# 09_FPGA_misc.net
KiCad netlist of a schematic drawn in Altium Designer
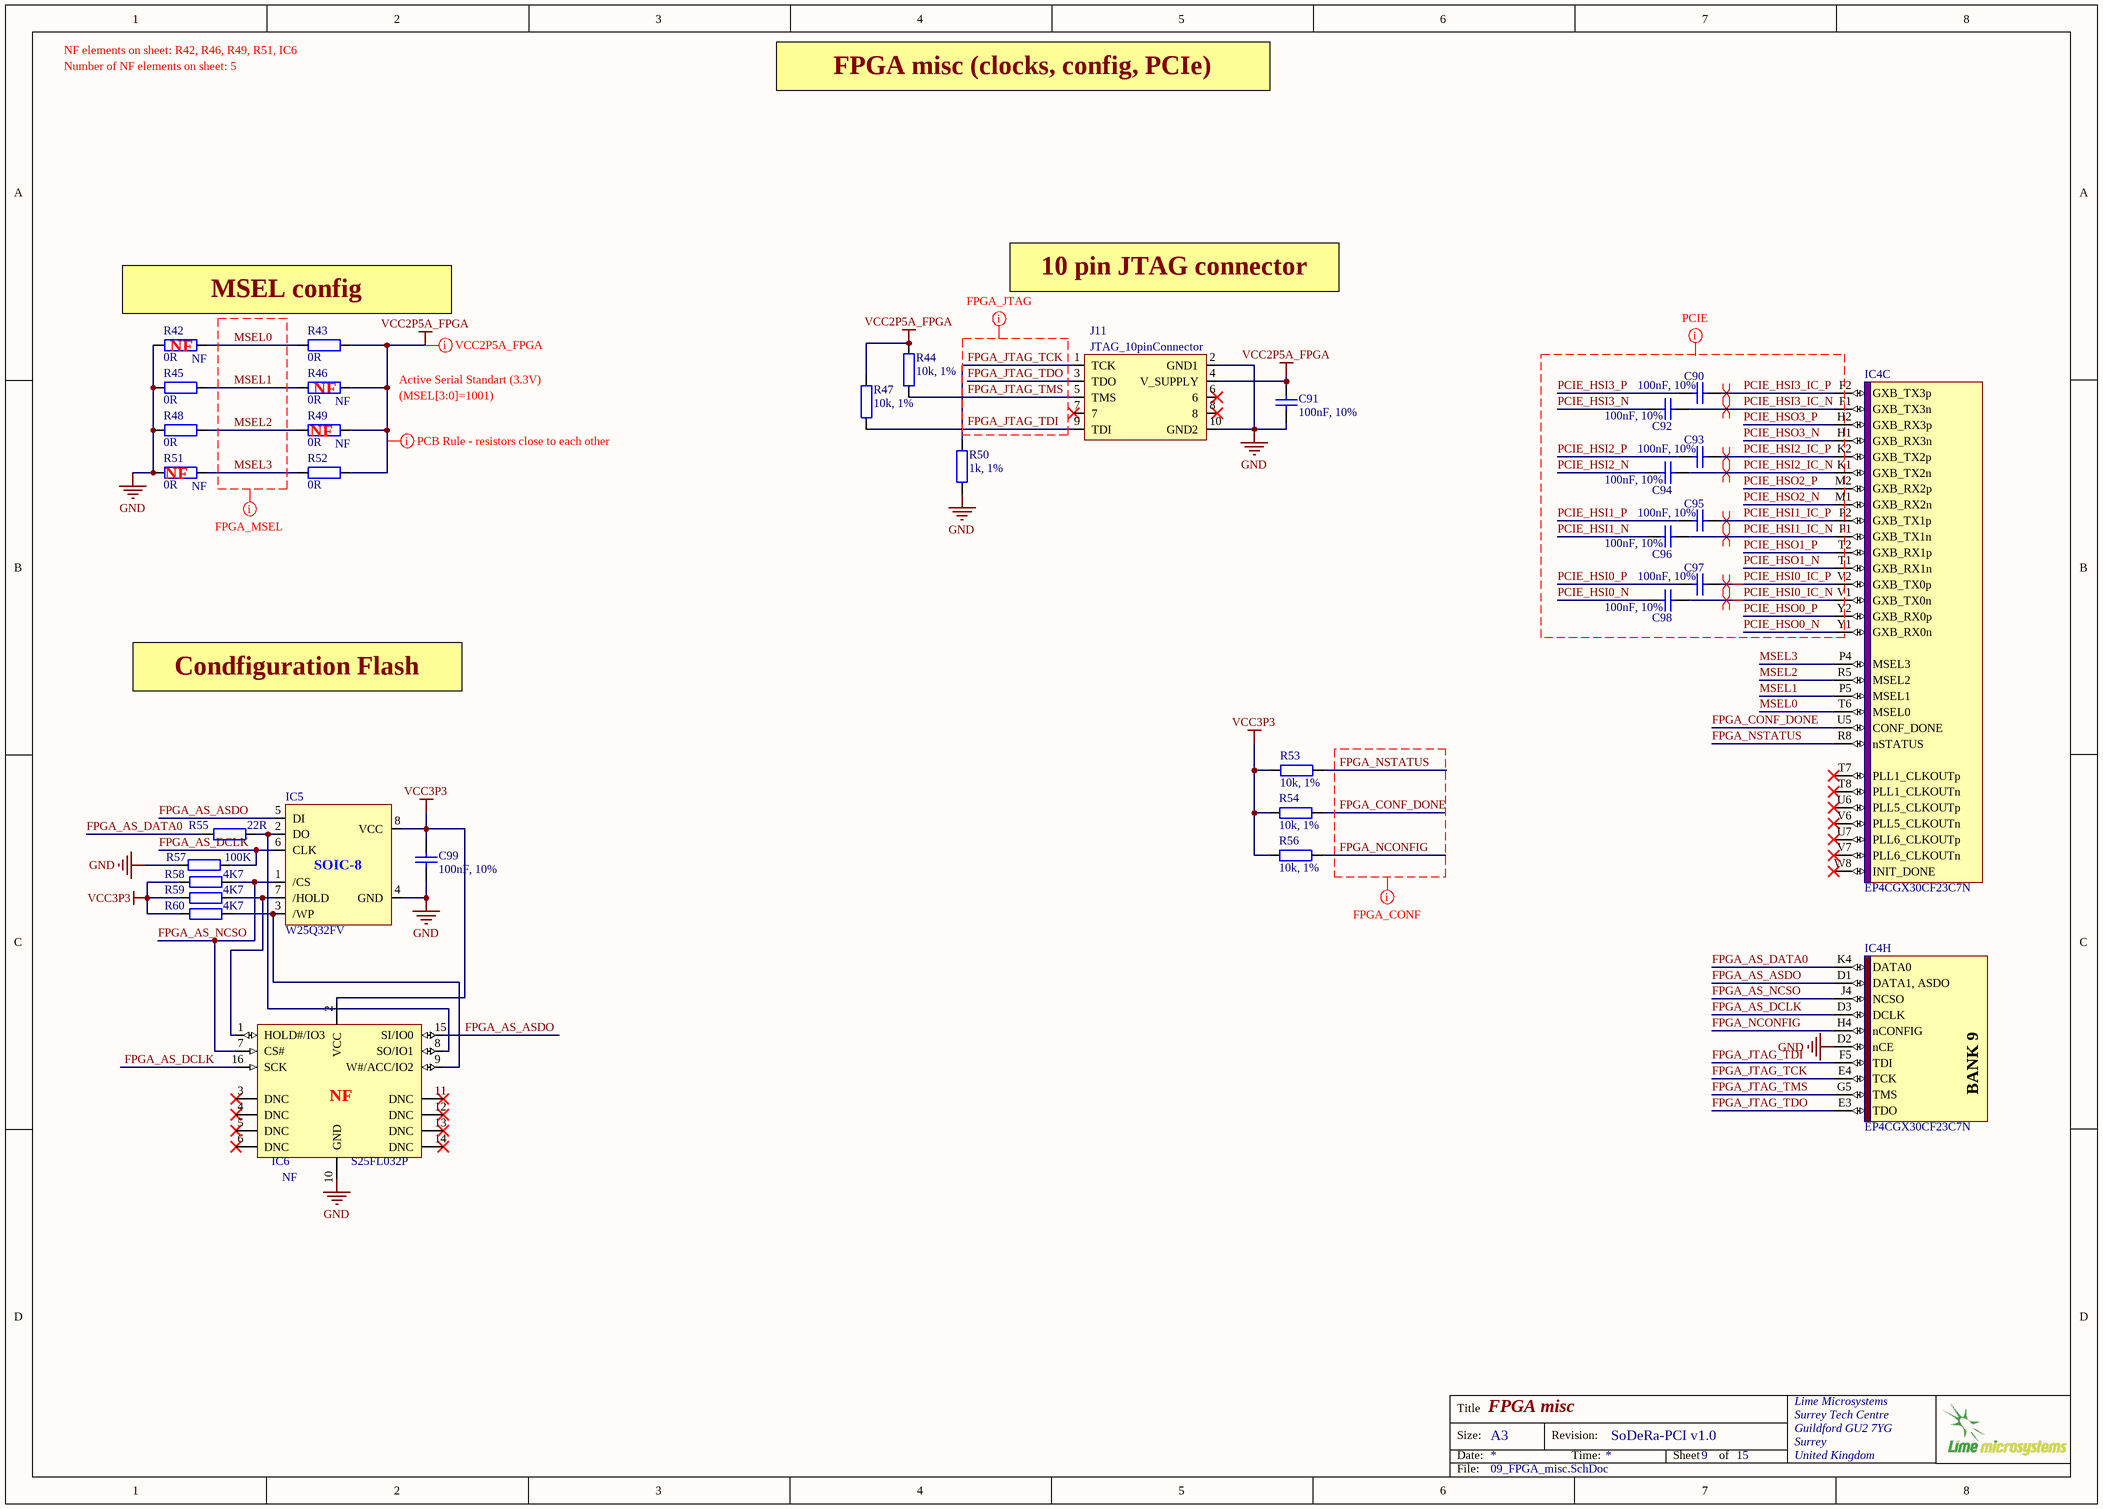
[diagram p0: 09_FPGA_misc.SchDoc]

(export (version "E")
  (design (tool "Eeschema 10.0.6"))
  (components
    (comp (ref "C90")
      (value "100nF, 10%")
      (footprint "LimeMicroAltiumLib_pcbLib:CAP0402")
      (fields (field (name "TOLERANCE") "10 %") (field (name "MANUFACTURER") "Murata"))
      (libsource (lib "LimeFPGAboard_schLib") (part "Cap_0603"))
    )
    (comp (ref "C91")
      (value "100nF, 10%")
      (footprint "LimeMicroAltiumLib_pcbLib:CAP0402")
      (fields (field (name "TOLERANCE") "10 %") (field (name "MANUFACTURER") "Murata"))
      (libsource (lib "LimeFPGAboard_schLib") (part "Cap_0603"))
    )
    (comp (ref "C92")
      (value "100nF, 10%")
      (footprint "LimeMicroAltiumLib_pcbLib:CAP0402")
      (fields (field (name "TOLERANCE") "10 %") (field (name "MANUFACTURER") "Murata"))
      (libsource (lib "LimeFPGAboard_schLib") (part "Cap_0603"))
    )
    (comp (ref "C93")
      (value "100nF, 10%")
      (footprint "LimeMicroAltiumLib_pcbLib:CAP0402")
      (fields (field (name "TOLERANCE") "10 %") (field (name "MANUFACTURER") "Murata"))
      (libsource (lib "LimeFPGAboard_schLib") (part "Cap_0603"))
    )
    (comp (ref "C94")
      (value "100nF, 10%")
      (footprint "LimeMicroAltiumLib_pcbLib:CAP0402")
      (fields (field (name "TOLERANCE") "10 %") (field (name "MANUFACTURER") "Murata"))
      (libsource (lib "LimeFPGAboard_schLib") (part "Cap_0603"))
    )
    (comp (ref "C95")
      (value "100nF, 10%")
      (footprint "LimeMicroAltiumLib_pcbLib:CAP0402")
      (fields (field (name "TOLERANCE") "10 %") (field (name "MANUFACTURER") "Murata"))
      (libsource (lib "LimeFPGAboard_schLib") (part "Cap_0603"))
    )
    (comp (ref "C96")
      (value "100nF, 10%")
      (footprint "LimeMicroAltiumLib_pcbLib:CAP0402")
      (fields (field (name "TOLERANCE") "10 %") (field (name "MANUFACTURER") "Murata"))
      (libsource (lib "LimeFPGAboard_schLib") (part "Cap_0603"))
    )
    (comp (ref "C97")
      (value "100nF, 10%")
      (footprint "LimeMicroAltiumLib_pcbLib:CAP0402")
      (fields (field (name "TOLERANCE") "10 %") (field (name "MANUFACTURER") "Murata"))
      (libsource (lib "LimeFPGAboard_schLib") (part "Cap_0603"))
    )
    (comp (ref "C98")
      (value "100nF, 10%")
      (footprint "LimeMicroAltiumLib_pcbLib:CAP0402")
      (fields (field (name "TOLERANCE") "10 %") (field (name "MANUFACTURER") "Murata"))
      (libsource (lib "LimeFPGAboard_schLib") (part "Cap_0603"))
    )
    (comp (ref "C99")
      (value "100nF, 10%")
      (footprint "LimeMicroAltiumLib_pcbLib:CAP0402")
      (fields
        (field (name "TOLERANCE") "10 %")
        (field (name "MANUFACTURER") "Murata")
        (field (name "MANUFACTURER PART NUMBER") "GRM155R71C104KA88D")
      )
      (libsource (lib "LimeFPGAboard_schLib") (part "Cap_0603"))
    )
    (comp (ref "IC4")
      (value "EP4CGX30CF23C7N")
      (footprint "LimeMicroAltiumLib_pcbLib:ALTR-FBGA484_A-200")
      (fields (field (name "MANUFACTURER") "Altera"))
      (libsource (lib "LimeMicroAltiumLib_schLib") (part "EP4CGX30CF23C7N"))
    )
    (comp (ref "IC5")
      (value "W25Q32FV")
      (footprint "SOIC127P600-8DL_v3")
      (fields (field (name "MANUFACTURER") "Winbond Electronics"))
      (libsource (lib "LimeMicroAltiumLib_schLib") (part "W25Q32FV"))
    )
    (comp (ref "IC6")
      (value "S25FL032P")
      (footprint "LimeMicroAltiumLib_pcbLib:SOIC16_WIDE")
      (fields (field (name "MANUFACTURER") "Spansion") (field (name "ASSEMBLY INFO") "NF"))
      (libsource (lib "LimeMicroAltiumLib_schLib") (part "S25FL032P"))
    )
    (comp (ref "J11")
      (value "JTAG_10pinConnector")
      (footprint "LimeMicroAltiumLib_pcbLib:HEADER5x2_SM")
      (libsource (lib "LimeFPGAboard_schLib") (part "JTAG_connector_10pin"))
    )
    (comp (ref "R42")
      (value "0R")
      (footprint "LimeMicroAltiumLib_pcbLib:RES0402")
      (fields (field (name "MANUFACTURER") "Yageo") (field (name "ASSEMBLY INFO") "NF"))
      (libsource (lib "LimeFPGAboard_schLib") (part "Res_0402"))
    )
    (comp (ref "R43")
      (value "0R")
      (footprint "LimeMicroAltiumLib_pcbLib:RES0402")
      (fields (field (name "MANUFACTURER") "Yageo"))
      (libsource (lib "LimeFPGAboard_schLib") (part "Res_0402"))
    )
    (comp (ref "R44")
      (value "10k, 1%")
      (footprint "LimeMicroAltiumLib_pcbLib:RES0402")
      (fields (field (name "MANUFACTURER") "Yageo") (field (name "TOLERANCE") "±1%"))
      (libsource (lib "LimeMicroAltiumLib_schLib") (part "Res_0402"))
    )
    (comp (ref "R45")
      (value "0R")
      (footprint "LimeMicroAltiumLib_pcbLib:RES0402")
      (fields (field (name "MANUFACTURER") "Yageo"))
      (libsource (lib "LimeFPGAboard_schLib") (part "Res_0402"))
    )
    (comp (ref "R46")
      (value "0R")
      (footprint "LimeMicroAltiumLib_pcbLib:RES0402")
      (fields (field (name "MANUFACTURER") "Yageo") (field (name "ASSEMBLY INFO") "NF"))
      (libsource (lib "LimeFPGAboard_schLib") (part "Res_0402"))
    )
    (comp (ref "R47")
      (value "10k, 1%")
      (footprint "LimeMicroAltiumLib_pcbLib:RES0402")
      (fields (field (name "MANUFACTURER") "Yageo") (field (name "TOLERANCE") "±1%"))
      (libsource (lib "LimeMicroAltiumLib_schLib") (part "Res_0402"))
    )
    (comp (ref "R48")
      (value "0R")
      (footprint "LimeMicroAltiumLib_pcbLib:RES0402")
      (fields (field (name "MANUFACTURER") "Yageo"))
      (libsource (lib "LimeFPGAboard_schLib") (part "Res_0402"))
    )
    (comp (ref "R49")
      (value "0R")
      (footprint "LimeMicroAltiumLib_pcbLib:RES0402")
      (fields (field (name "MANUFACTURER") "Yageo") (field (name "ASSEMBLY INFO") "NF"))
      (libsource (lib "LimeFPGAboard_schLib") (part "Res_0402"))
    )
    (comp (ref "R50")
      (value "1k, 1%")
      (footprint "LimeMicroAltiumLib_pcbLib:RES0402")
      (fields (field (name "MANUFACTURER") "Stackpole Electronics Inc") (field (name "TOLERANCE") "±1%"))
      (libsource (lib "LimeMicroAltiumLib_schLib") (part "Res_0402"))
    )
    (comp (ref "R51")
      (value "0R")
      (footprint "LimeMicroAltiumLib_pcbLib:RES0402")
      (fields (field (name "MANUFACTURER") "Yageo") (field (name "ASSEMBLY INFO") "NF"))
      (libsource (lib "LimeFPGAboard_schLib") (part "Res_0402"))
    )
    (comp (ref "R52")
      (value "0R")
      (footprint "LimeMicroAltiumLib_pcbLib:RES0402")
      (fields (field (name "MANUFACTURER") "Yageo"))
      (libsource (lib "LimeFPGAboard_schLib") (part "Res_0402"))
    )
    (comp (ref "R53")
      (value "10k, 1%")
      (footprint "LimeMicroAltiumLib_pcbLib:RES0402")
      (fields (field (name "MANUFACTURER") "Yageo") (field (name "TOLERANCE") "±1%"))
      (libsource (lib "LimeMicroAltiumLib_schLib") (part "Res_0402"))
    )
    (comp (ref "R54")
      (value "10k, 1%")
      (footprint "LimeMicroAltiumLib_pcbLib:RES0402")
      (fields (field (name "MANUFACTURER") "Yageo") (field (name "TOLERANCE") "±1%"))
      (libsource (lib "LimeMicroAltiumLib_schLib") (part "Res_0402"))
    )
    (comp (ref "R55")
      (value "22R")
      (footprint "LimeMicroAltiumLib_pcbLib:RES0402")
      (fields (field (name "TOLERANCE") "±1%"))
      (libsource (lib "LimeFPGAboard_schLib") (part "Res_0402"))
    )
    (comp (ref "R56")
      (value "10k, 1%")
      (footprint "LimeMicroAltiumLib_pcbLib:RES0402")
      (fields (field (name "MANUFACTURER") "Yageo") (field (name "TOLERANCE") "±1%"))
      (libsource (lib "LimeMicroAltiumLib_schLib") (part "Res_0402"))
    )
    (comp (ref "R57")
      (value "100K")
      (footprint "LimeMicroAltiumLib_pcbLib:RES0402")
      (fields
        (field (name "TOLERANCE") "±5%")
        (field (name "MANUFACTURER") "Panasonic Electronic Components")
      )
      (libsource (lib "LimeFPGAboard_schLib") (part "Res_0402"))
    )
    (comp (ref "R58")
      (value "4K7")
      (footprint "LimeMicroAltiumLib_pcbLib:RES0402")
      (fields (field (name "TOLERANCE") "±5%"))
      (libsource (lib "LimeFPGAboard_schLib") (part "Res_0402"))
    )
    (comp (ref "R59")
      (value "4K7")
      (footprint "LimeMicroAltiumLib_pcbLib:RES0402")
      (fields (field (name "TOLERANCE") "±5%"))
      (libsource (lib "LimeFPGAboard_schLib") (part "Res_0402"))
    )
    (comp (ref "R60")
      (value "4K7")
      (footprint "LimeMicroAltiumLib_pcbLib:RES0402")
      (fields (field (name "TOLERANCE") "±5%"))
      (libsource (lib "LimeFPGAboard_schLib") (part "Res_0402"))
    )
  )
  (nets
    (net (code "1") (name "/FPGA_AS_ASDO") (class "Default")
      (node (ref "IC4") (pin "D1") (pinfunction "DATA1,_ASDO_D1") (pintype "bidirectional"))
      (node (ref "IC5") (pin "5") (pinfunction "DI_5") (pintype "passive"))
      (node (ref "IC6") (pin "15") (pinfunction "SI/IO0_15") (pintype "bidirectional"))
    )
    (net (code "2") (name "/FPGA_AS_DATA0") (class "Default")
      (node (ref "IC4") (pin "K4") (pinfunction "DATA0_K4") (pintype "bidirectional"))
      (node (ref "R55") (pin "2") (pinfunction "2_2") (pintype "passive"))
    )
    (net (code "3") (name "/FPGA_AS_DCLK") (class "Default")
      (node (ref "IC4") (pin "D3") (pinfunction "DCLK_D3") (pintype "bidirectional"))
      (node (ref "IC5") (pin "6") (pinfunction "CLK_6") (pintype "passive"))
      (node (ref "IC6") (pin "16") (pinfunction "SCK_16") (pintype "input"))
      (node (ref "R57") (pin "1") (pinfunction "1_1") (pintype "passive"))
    )
    (net (code "4") (name "/FPGA_AS_NCSO") (class "Default")
      (node (ref "IC4") (pin "J4") (pinfunction "NCSO_J4") (pintype "bidirectional"))
      (node (ref "IC5") (pin "1") (pinfunction "/CS_1") (pintype "passive"))
      (node (ref "IC6") (pin "7") (pinfunction "CS#_7") (pintype "input"))
      (node (ref "R58") (pin "2") (pinfunction "2_2") (pintype "passive"))
    )
    (net (code "5") (name "/FPGA_CONF_DONE") (class "Default")
      (node (ref "IC4") (pin "U5") (pinfunction "CONF_DONE_U5") (pintype "bidirectional"))
      (node (ref "R54") (pin "2") (pinfunction "2_2") (pintype "passive"))
    )
    (net (code "6") (name "/FPGA_JTAG_TCK") (class "Default")
      (node (ref "IC4") (pin "E4") (pinfunction "TCK_E4") (pintype "bidirectional"))
      (node (ref "J11") (pin "1") (pinfunction "TCK_1") (pintype "passive"))
      (node (ref "R50") (pin "1") (pinfunction "1_1") (pintype "passive"))
    )
    (net (code "7") (name "/FPGA_JTAG_TDI") (class "Default")
      (node (ref "IC4") (pin "F5") (pinfunction "TDI_F5") (pintype "bidirectional"))
      (node (ref "J11") (pin "9") (pinfunction "TDI_9") (pintype "passive"))
      (node (ref "R47") (pin "2") (pinfunction "2_2") (pintype "passive"))
    )
    (net (code "8") (name "/FPGA_JTAG_TDO") (class "Default")
      (node (ref "IC4") (pin "E3") (pinfunction "TDO_E3") (pintype "bidirectional"))
      (node (ref "J11") (pin "3") (pinfunction "TDO_3") (pintype "passive"))
    )
    (net (code "9") (name "/FPGA_JTAG_TMS") (class "Default")
      (node (ref "IC4") (pin "G5") (pinfunction "TMS_G5") (pintype "bidirectional"))
      (node (ref "J11") (pin "5") (pinfunction "TMS_5") (pintype "passive"))
      (node (ref "R44") (pin "2") (pinfunction "2_2") (pintype "passive"))
    )
    (net (code "10") (name "/FPGA_NCONFIG") (class "Default")
      (node (ref "IC4") (pin "H4") (pinfunction "nCONFIG_H4") (pintype "bidirectional"))
      (node (ref "R56") (pin "2") (pinfunction "2_2") (pintype "passive"))
    )
    (net (code "11") (name "/FPGA_NSTATUS") (class "Default")
      (node (ref "IC4") (pin "R8") (pinfunction "nSTATUS_R8") (pintype "bidirectional"))
      (node (ref "R53") (pin "2") (pinfunction "2_2") (pintype "passive"))
    )
    (net (code "12") (name "/MSEL0") (class "Default")
      (node (ref "IC4") (pin "T6") (pinfunction "MSEL0_T6") (pintype "bidirectional"))
      (node (ref "R42") (pin "1") (pinfunction "1_1") (pintype "passive"))
      (node (ref "R43") (pin "2") (pinfunction "2_2") (pintype "passive"))
    )
    (net (code "13") (name "/MSEL1") (class "Default")
      (node (ref "IC4") (pin "P5") (pinfunction "MSEL1_P5") (pintype "bidirectional"))
      (node (ref "R45") (pin "1") (pinfunction "1_1") (pintype "passive"))
      (node (ref "R46") (pin "2") (pinfunction "2_2") (pintype "passive"))
    )
    (net (code "14") (name "/MSEL2") (class "Default")
      (node (ref "IC4") (pin "R5") (pinfunction "MSEL2_R5") (pintype "bidirectional"))
      (node (ref "R48") (pin "1") (pinfunction "1_1") (pintype "passive"))
      (node (ref "R49") (pin "2") (pinfunction "2_2") (pintype "passive"))
    )
    (net (code "15") (name "/MSEL3") (class "Default")
      (node (ref "IC4") (pin "P4") (pinfunction "MSEL3_P4") (pintype "bidirectional"))
      (node (ref "R51") (pin "1") (pinfunction "1_1") (pintype "passive"))
      (node (ref "R52") (pin "2") (pinfunction "2_2") (pintype "passive"))
    )
    (net (code "16") (name "/PCIE_HSI0_IC_N") (class "Default")
      (node (ref "C98") (pin "1") (pinfunction "1_1") (pintype "passive"))
      (node (ref "IC4") (pin "V1") (pinfunction "GXB_TX0n_V1") (pintype "bidirectional"))
    )
    (net (code "17") (name "/PCIE_HSI0_IC_P") (class "Default")
      (node (ref "C97") (pin "1") (pinfunction "1_1") (pintype "passive"))
      (node (ref "IC4") (pin "V2") (pinfunction "GXB_TX0p_V2") (pintype "bidirectional"))
    )
    (net (code "18") (name "/PCIE_HSI0_N") (class "Default")
      (node (ref "C98") (pin "2") (pinfunction "2_2") (pintype "passive"))
    )
    (net (code "19") (name "/PCIE_HSI0_P") (class "Default")
      (node (ref "C97") (pin "2") (pinfunction "2_2") (pintype "passive"))
    )
    (net (code "20") (name "/PCIE_HSI1_IC_N") (class "Default")
      (node (ref "C96") (pin "1") (pinfunction "1_1") (pintype "passive"))
      (node (ref "IC4") (pin "P1") (pinfunction "GXB_TX1n_P1") (pintype "bidirectional"))
    )
    (net (code "21") (name "/PCIE_HSI1_IC_P") (class "Default")
      (node (ref "C95") (pin "1") (pinfunction "1_1") (pintype "passive"))
      (node (ref "IC4") (pin "P2") (pinfunction "GXB_TX1p_P2") (pintype "bidirectional"))
    )
    (net (code "22") (name "/PCIE_HSI1_N") (class "Default")
      (node (ref "C96") (pin "2") (pinfunction "2_2") (pintype "passive"))
    )
    (net (code "23") (name "/PCIE_HSI1_P") (class "Default")
      (node (ref "C95") (pin "2") (pinfunction "2_2") (pintype "passive"))
    )
    (net (code "24") (name "/PCIE_HSI2_IC_N") (class "Default")
      (node (ref "C94") (pin "1") (pinfunction "1_1") (pintype "passive"))
      (node (ref "IC4") (pin "K1") (pinfunction "GXB_TX2n_K1") (pintype "bidirectional"))
    )
    (net (code "25") (name "/PCIE_HSI2_IC_P") (class "Default")
      (node (ref "C93") (pin "1") (pinfunction "1_1") (pintype "passive"))
      (node (ref "IC4") (pin "K2") (pinfunction "GXB_TX2p_K2") (pintype "bidirectional"))
    )
    (net (code "26") (name "/PCIE_HSI2_N") (class "Default")
      (node (ref "C94") (pin "2") (pinfunction "2_2") (pintype "passive"))
    )
    (net (code "27") (name "/PCIE_HSI2_P") (class "Default")
      (node (ref "C93") (pin "2") (pinfunction "2_2") (pintype "passive"))
    )
    (net (code "28") (name "/PCIE_HSI3_IC_N") (class "Default")
      (node (ref "C92") (pin "1") (pinfunction "1_1") (pintype "passive"))
      (node (ref "IC4") (pin "F1") (pinfunction "GXB_TX3n_F1") (pintype "bidirectional"))
    )
    (net (code "29") (name "/PCIE_HSI3_IC_P") (class "Default")
      (node (ref "C90") (pin "1") (pinfunction "1_1") (pintype "passive"))
      (node (ref "IC4") (pin "F2") (pinfunction "GXB_TX3p_F2") (pintype "bidirectional"))
    )
    (net (code "30") (name "/PCIE_HSI3_N") (class "Default")
      (node (ref "C92") (pin "2") (pinfunction "2_2") (pintype "passive"))
    )
    (net (code "31") (name "/PCIE_HSI3_P") (class "Default")
      (node (ref "C90") (pin "2") (pinfunction "2_2") (pintype "passive"))
    )
    (net (code "32") (name "/PCIE_HSO0_N") (class "Default")
      (node (ref "IC4") (pin "Y1") (pinfunction "GXB_RX0n_Y1") (pintype "bidirectional"))
    )
    (net (code "33") (name "/PCIE_HSO0_P") (class "Default")
      (node (ref "IC4") (pin "Y2") (pinfunction "GXB_RX0p_Y2") (pintype "bidirectional"))
    )
    (net (code "34") (name "/PCIE_HSO1_N") (class "Default")
      (node (ref "IC4") (pin "T1") (pinfunction "GXB_RX1n_T1") (pintype "bidirectional"))
    )
    (net (code "35") (name "/PCIE_HSO1_P") (class "Default")
      (node (ref "IC4") (pin "T2") (pinfunction "GXB_RX1p_T2") (pintype "bidirectional"))
    )
    (net (code "36") (name "/PCIE_HSO2_N") (class "Default")
      (node (ref "IC4") (pin "M1") (pinfunction "GXB_RX2n_M1") (pintype "bidirectional"))
    )
    (net (code "37") (name "/PCIE_HSO2_P") (class "Default")
      (node (ref "IC4") (pin "M2") (pinfunction "GXB_RX2p_M2") (pintype "bidirectional"))
    )
    (net (code "38") (name "/PCIE_HSO3_N") (class "Default")
      (node (ref "IC4") (pin "H1") (pinfunction "GXB_RX3n_H1") (pintype "bidirectional"))
    )
    (net (code "39") (name "/PCIE_HSO3_P") (class "Default")
      (node (ref "IC4") (pin "H2") (pinfunction "GXB_RX3p_H2") (pintype "bidirectional"))
    )
    (net (code "40") (name "GND") (class "Default")
      (node (ref "C91") (pin "2") (pinfunction "2_2") (pintype "passive"))
      (node (ref "C99") (pin "2") (pinfunction "2_2") (pintype "passive"))
      (node (ref "IC4") (pin "D2") (pinfunction "nCE_D2") (pintype "bidirectional"))
      (node (ref "IC5") (pin "4") (pinfunction "GND_4") (pintype "passive"))
      (node (ref "IC6") (pin "10") (pinfunction "GND_10") (pintype "passive"))
      (node (ref "J11") (pin "10") (pinfunction "GND2_10") (pintype "power_in"))
      (node (ref "J11") (pin "2") (pinfunction "GND1_2") (pintype "power_in"))
      (node (ref "R42") (pin "2") (pinfunction "2_2") (pintype "passive"))
      (node (ref "R45") (pin "2") (pinfunction "2_2") (pintype "passive"))
      (node (ref "R48") (pin "2") (pinfunction "2_2") (pintype "passive"))
      (node (ref "R50") (pin "2") (pinfunction "2_2") (pintype "passive"))
      (node (ref "R51") (pin "2") (pinfunction "2_2") (pintype "passive"))
      (node (ref "R57") (pin "2") (pinfunction "2_2") (pintype "passive"))
    )
    (net (code "41") (name "Net-(IC5-DO)") (class "Default")
      (node (ref "IC5") (pin "2") (pinfunction "DO_2") (pintype "passive"))
      (node (ref "IC6") (pin "8") (pinfunction "SO/IO1_8") (pintype "bidirectional"))
      (node (ref "R55") (pin "1") (pinfunction "1_1") (pintype "passive"))
    )
    (net (code "42") (name "Net-(IC5-{slash}HOLD)") (class "Default")
      (node (ref "IC5") (pin "7") (pinfunction "/HOLD_7") (pintype "passive"))
      (node (ref "IC6") (pin "1") (pinfunction "HOLD#/IO3_1") (pintype "bidirectional"))
      (node (ref "R59") (pin "2") (pinfunction "2_2") (pintype "passive"))
    )
    (net (code "43") (name "Net-(IC5-{slash}WP)") (class "Default")
      (node (ref "IC5") (pin "3") (pinfunction "/WP_3") (pintype "passive"))
      (node (ref "IC6") (pin "9") (pinfunction "W#/ACC/IO2_9") (pintype "bidirectional"))
      (node (ref "R60") (pin "2") (pinfunction "2_2") (pintype "passive"))
    )
    (net (code "44") (name "VCC2P5A_FPGA") (class "Default")
      (node (ref "C91") (pin "1") (pinfunction "1_1") (pintype "passive"))
      (node (ref "J11") (pin "4") (pinfunction "V_SUPPLY_4") (pintype "power_in"))
      (node (ref "R43") (pin "1") (pinfunction "1_1") (pintype "passive"))
      (node (ref "R44") (pin "1") (pinfunction "1_1") (pintype "passive"))
      (node (ref "R46") (pin "1") (pinfunction "1_1") (pintype "passive"))
      (node (ref "R47") (pin "1") (pinfunction "1_1") (pintype "passive"))
      (node (ref "R49") (pin "1") (pinfunction "1_1") (pintype "passive"))
      (node (ref "R52") (pin "1") (pinfunction "1_1") (pintype "passive"))
    )
    (net (code "45") (name "VCC3P3") (class "Default")
      (node (ref "C99") (pin "1") (pinfunction "1_1") (pintype "passive"))
      (node (ref "IC5") (pin "8") (pinfunction "VCC_8") (pintype "passive"))
      (node (ref "IC6") (pin "2") (pinfunction "VCC_2") (pintype "power_in"))
      (node (ref "R53") (pin "1") (pinfunction "1_1") (pintype "passive"))
      (node (ref "R54") (pin "1") (pinfunction "1_1") (pintype "passive"))
      (node (ref "R56") (pin "1") (pinfunction "1_1") (pintype "passive"))
      (node (ref "R58") (pin "1") (pinfunction "1_1") (pintype "passive"))
      (node (ref "R59") (pin "1") (pinfunction "1_1") (pintype "passive"))
      (node (ref "R60") (pin "1") (pinfunction "1_1") (pintype "passive"))
    )
    (net (code "46") (name "unconnected-(IC4C-INIT_DONE-PadW8)") (class "Default")
      (node (ref "IC4") (pin "W8") (pinfunction "INIT_DONE_W8") (pintype "bidirectional+no_connect"))
    )
    (net (code "47") (name "unconnected-(IC4C-PLL1_CLKOUTn-PadT8)") (class "Default")
      (node (ref "IC4") (pin "T8") (pinfunction "PLL1_CLKOUTn_T8") (pintype "bidirectional+no_connect"))
    )
    (net (code "48") (name "unconnected-(IC4C-PLL1_CLKOUTp-PadT7)") (class "Default")
      (node (ref "IC4") (pin "T7") (pinfunction "PLL1_CLKOUTp_T7") (pintype "bidirectional+no_connect"))
    )
    (net (code "49") (name "unconnected-(IC4C-PLL5_CLKOUTn-PadV6)") (class "Default")
      (node (ref "IC4") (pin "V6") (pinfunction "PLL5_CLKOUTn_V6") (pintype "bidirectional+no_connect"))
    )
    (net (code "50") (name "unconnected-(IC4C-PLL5_CLKOUTp-PadU6)") (class "Default")
      (node (ref "IC4") (pin "U6") (pinfunction "PLL5_CLKOUTp_U6") (pintype "bidirectional+no_connect"))
    )
    (net (code "51") (name "unconnected-(IC4C-PLL6_CLKOUTn-PadV7)") (class "Default")
      (node (ref "IC4") (pin "V7") (pinfunction "PLL6_CLKOUTn_V7") (pintype "bidirectional+no_connect"))
    )
    (net (code "52") (name "unconnected-(IC4C-PLL6_CLKOUTp-PadU7)") (class "Default")
      (node (ref "IC4") (pin "U7") (pinfunction "PLL6_CLKOUTp_U7") (pintype "bidirectional+no_connect"))
    )
    (net (code "53") (name "unconnected-(IC6-DNC-Pad3)") (class "Default")
      (node (ref "IC6") (pin "3") (pinfunction "DNC_3") (pintype "passive+no_connect"))
    )
    (net (code "54") (name "unconnected-(IC6-DNC-Pad4)") (class "Default")
      (node (ref "IC6") (pin "4") (pinfunction "DNC_4") (pintype "passive+no_connect"))
    )
    (net (code "55") (name "unconnected-(IC6-DNC-Pad5)") (class "Default")
      (node (ref "IC6") (pin "5") (pinfunction "DNC_5") (pintype "passive+no_connect"))
    )
    (net (code "56") (name "unconnected-(IC6-DNC-Pad6)") (class "Default")
      (node (ref "IC6") (pin "6") (pinfunction "DNC_6") (pintype "passive+no_connect"))
    )
    (net (code "57") (name "unconnected-(IC6-DNC-Pad11)") (class "Default")
      (node (ref "IC6") (pin "11") (pinfunction "DNC_11") (pintype "passive+no_connect"))
    )
    (net (code "58") (name "unconnected-(IC6-DNC-Pad12)") (class "Default")
      (node (ref "IC6") (pin "12") (pinfunction "DNC_12") (pintype "passive+no_connect"))
    )
    (net (code "59") (name "unconnected-(IC6-DNC-Pad13)") (class "Default")
      (node (ref "IC6") (pin "13") (pinfunction "DNC_13") (pintype "passive+no_connect"))
    )
    (net (code "60") (name "unconnected-(IC6-DNC-Pad14)") (class "Default")
      (node (ref "IC6") (pin "14") (pinfunction "DNC_14") (pintype "passive+no_connect"))
    )
    (net (code "61") (name "unconnected-(J11-Pad6)") (class "Default")
      (node (ref "J11") (pin "6") (pinfunction "6_6") (pintype "passive+no_connect"))
    )
    (net (code "62") (name "unconnected-(J11-Pad7)") (class "Default")
      (node (ref "J11") (pin "7") (pinfunction "7_7") (pintype "passive+no_connect"))
    )
    (net (code "63") (name "unconnected-(J11-Pad8)") (class "Default")
      (node (ref "J11") (pin "8") (pinfunction "8_8") (pintype "passive+no_connect"))
    )
  )
)
